# 13_Others.net
KiCad netlist of a schematic drawn in Altium Designer
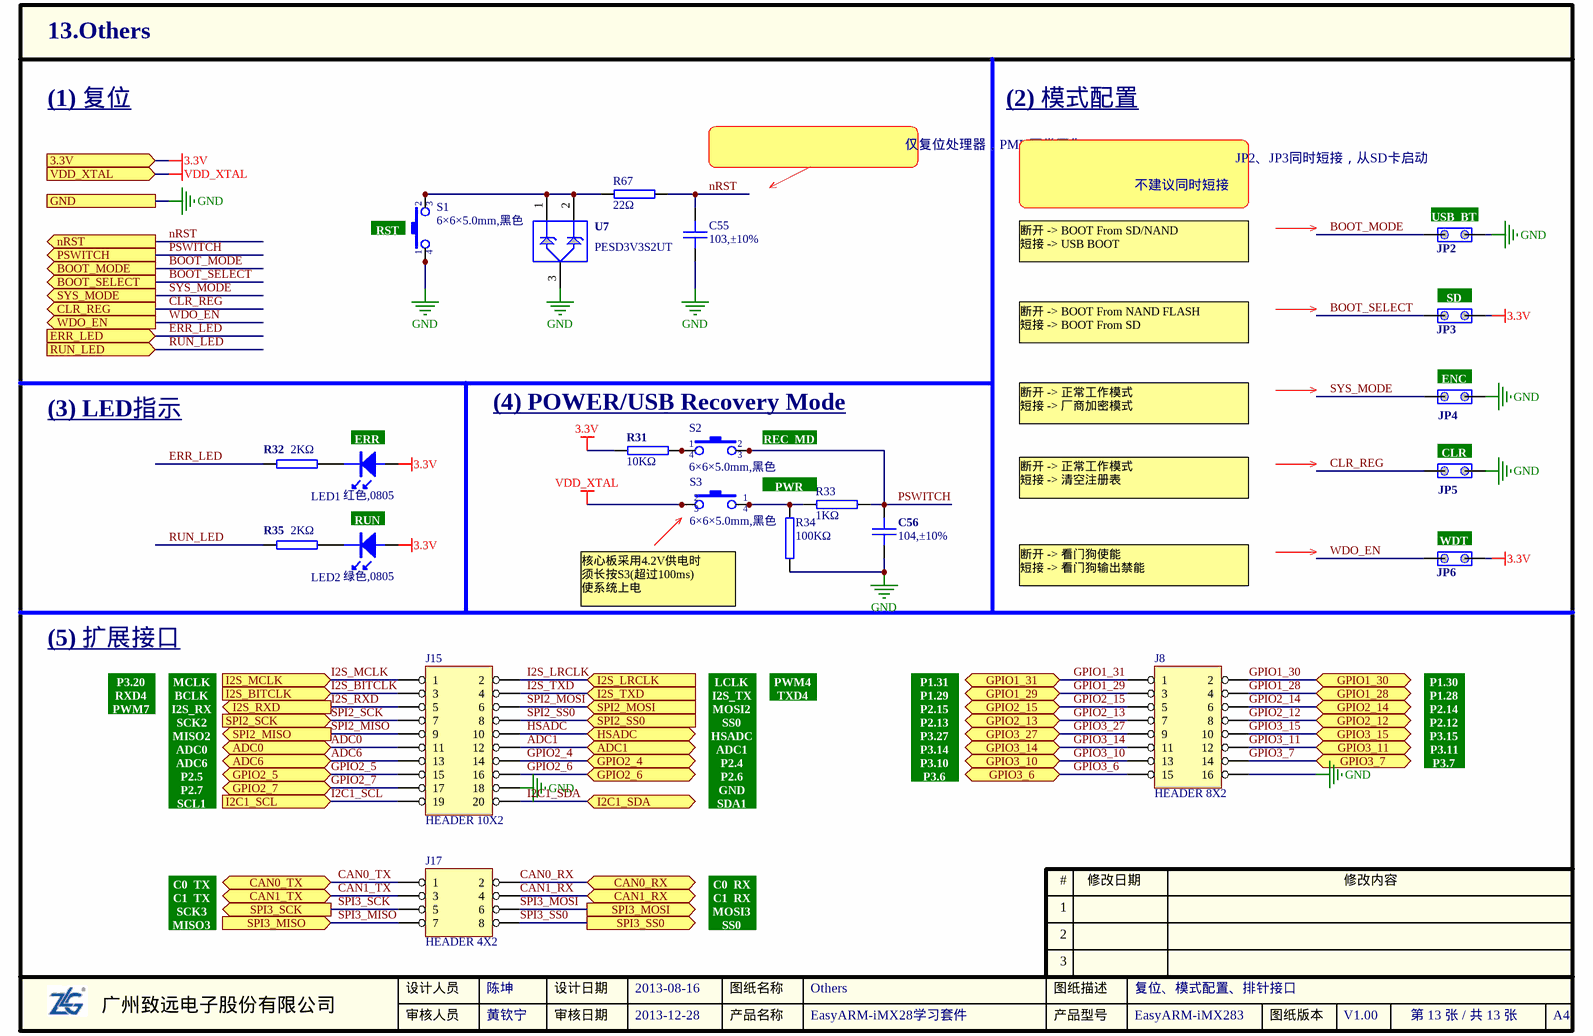
[diagram p0: 13. Others.SchDoc]

(export (version "E")
  (design (tool "Eeschema 10.0.6"))
  (components
    (comp (ref "C55")
      (value "103,±10%")
      (footprint "0603C")
      (description "103,±10%,50V,X7R,0603,*,RoHS")
      (libsource (lib "ErpMaterialData") (part "CAP1"))
    )
    (comp (ref "C56")
      (value "104,±10%")
      (footprint "0603C")
      (description "104,±10%,50V,X7R,0603,*,RoHS")
      (libsource (lib "ErpMaterialData") (part "CAP1"))
    )
    (comp (ref "J8")
      (value "HEADER 8X2")
      (footprint "IDC-16")
      (libsource (lib "无需物料号元件") (part "HEADER 8X2"))
    )
    (comp (ref "J15")
      (value "HEADER 10X2")
      (footprint "IDC-20")
      (libsource (lib "无需物料号元件") (part "HEADER 10X2"))
    )
    (comp (ref "J17")
      (value "HEADER 4X2")
      (footprint "IDC-8")
      (libsource (lib "无需物料号元件") (part "HEADER 4X2"))
    )
    (comp (ref "JP2") (value "120Ω_EN") (footprint "SIP-2") (libsource (lib "无需物料号元件") (part "JMP2")))
    (comp (ref "JP3") (value "120Ω_EN") (footprint "SIP-2") (libsource (lib "无需物料号元件") (part "JMP2")))
    (comp (ref "JP4") (value "120Ω_EN") (footprint "SIP-2") (libsource (lib "无需物料号元件") (part "JMP2")))
    (comp (ref "JP5") (value "120Ω_EN") (footprint "SIP-2") (libsource (lib "无需物料号元件") (part "JMP2")))
    (comp (ref "JP6") (value "120Ω_EN") (footprint "SIP-2") (libsource (lib "无需物料号元件") (part "JMP2")))
    (comp (ref "LED1")
      (value "红色,0805")
      (footprint "LED-0805")
      (description "红色,0805,0805,RoHS")
      (fields (field (name "Comment") "LED1"))
      (libsource (lib "ErpMaterialData") (part "LED1"))
    )
    (comp (ref "LED2")
      (value "绿色,0805")
      (footprint "LED-0805")
      (description "绿色,0805,0805,RoHS")
      (fields (field (name "Comment") "LED1"))
      (libsource (lib "ErpMaterialData") (part "LED1"))
    )
    (comp (ref "R31")
      (value "10KΩ")
      (footprint "0603R")
      (description "10KΩ,0603,*,RoHS")
      (libsource (lib "ErpMaterialData") (part "RES2"))
    )
    (comp (ref "R32")
      (value "2KΩ")
      (footprint "0603R")
      (description "2KΩ,0603,*,RoHS")
      (libsource (lib "ErpMaterialData") (part "RES2"))
    )
    (comp (ref "R33")
      (value "1KΩ")
      (footprint "0603R")
      (description "1KΩ,0603,*,RoHS")
      (libsource (lib "ErpMaterialData") (part "RES2"))
    )
    (comp (ref "R34")
      (value "100KΩ")
      (footprint "0603R")
      (description "100KΩ,0603,*,RoHS")
      (libsource (lib "ErpMaterialData") (part "RES2"))
    )
    (comp (ref "R35")
      (value "2KΩ")
      (footprint "0603R")
      (description "2KΩ,0603,*,RoHS")
      (libsource (lib "ErpMaterialData") (part "RES2"))
    )
    (comp (ref "R67") (value "22Ω") (footprint "0603R") (libsource (lib "ErpMaterialData") (part "RES2")))
    (comp (ref "S1")
      (value "6×6×5.0mm,黑色")
      (footprint "KEY-6S")
      (description "6×6×5.0mm,黑色,SMD,,*")
      (fields (field (name "Comment") "SW-PB4P"))
      (libsource (lib "ErpMaterialData") (part "SW-PB4P"))
    )
    (comp (ref "S2")
      (value "6×6×5.0mm,黑色")
      (footprint "KEY-6S")
      (description "6×6×5.0mm,黑色,SMD,,*")
      (fields (field (name "Comment") "SW-PB4P"))
      (libsource (lib "ErpMaterialData") (part "SW-PB4P"))
    )
    (comp (ref "S3")
      (value "6×6×5.0mm,黑色")
      (footprint "KEY-6S")
      (description "6×6×5.0mm,黑色,SMD,,*")
      (fields (field (name "Comment") "SW-PB4P"))
      (libsource (lib "ErpMaterialData") (part "SW-PB4P"))
    )
    (comp (ref "U7")
      (value "PESD3V3S2UT")
      (footprint "SOT-23")
      (description "ESD单向")
      (fields (field (name "Comment") "ESD-3"))
      (libsource (lib "ErpMaterialData") (part "ESD-3"))
    )
  )
  (nets
    (net (code "1") (name "/ADC0") (class "Default")
      (node (ref "J15") (pin "11") (pinfunction "11_11") (pintype "passive"))
    )
    (net (code "2") (name "/ADC1") (class "Default")
      (node (ref "J15") (pin "12") (pinfunction "12_12") (pintype "passive"))
    )
    (net (code "3") (name "/ADC6") (class "Default")
      (node (ref "J15") (pin "13") (pinfunction "13_13") (pintype "passive"))
    )
    (net (code "4") (name "/BOOT_MODE") (class "Default")
      (node (ref "JP2") (pin "1") (pinfunction "1_1") (pintype "passive"))
    )
    (net (code "5") (name "/BOOT_SELECT") (class "Default")
      (node (ref "JP3") (pin "1") (pinfunction "1_1") (pintype "passive"))
    )
    (net (code "6") (name "/CAN0_RX") (class "Default")
      (node (ref "J17") (pin "2") (pinfunction "2_2") (pintype "passive"))
    )
    (net (code "7") (name "/CAN0_TX") (class "Default")
      (node (ref "J17") (pin "1") (pinfunction "1_1") (pintype "passive"))
    )
    (net (code "8") (name "/CAN1_RX") (class "Default")
      (node (ref "J17") (pin "4") (pinfunction "4_4") (pintype "passive"))
    )
    (net (code "9") (name "/CAN1_TX") (class "Default")
      (node (ref "J17") (pin "3") (pinfunction "3_3") (pintype "passive"))
    )
    (net (code "10") (name "/CLR_REG") (class "Default")
      (node (ref "JP5") (pin "1") (pinfunction "1_1") (pintype "passive"))
    )
    (net (code "11") (name "/ERR_LED") (class "Default")
      (node (ref "R32") (pin "1") (pinfunction "1_1") (pintype "passive"))
    )
    (net (code "12") (name "/GPIO1_28") (class "Default")
      (node (ref "J8") (pin "4") (pinfunction "4_4") (pintype "passive"))
    )
    (net (code "13") (name "/GPIO1_29") (class "Default")
      (node (ref "J8") (pin "3") (pinfunction "3_3") (pintype "passive"))
    )
    (net (code "14") (name "/GPIO1_30") (class "Default")
      (node (ref "J8") (pin "2") (pinfunction "2_2") (pintype "passive"))
    )
    (net (code "15") (name "/GPIO1_31") (class "Default")
      (node (ref "J8") (pin "1") (pinfunction "1_1") (pintype "passive"))
    )
    (net (code "16") (name "/GPIO2_4") (class "Default")
      (node (ref "J15") (pin "14") (pinfunction "14_14") (pintype "passive"))
    )
    (net (code "17") (name "/GPIO2_5") (class "Default")
      (node (ref "J15") (pin "15") (pinfunction "15_15") (pintype "passive"))
    )
    (net (code "18") (name "/GPIO2_6") (class "Default")
      (node (ref "J15") (pin "16") (pinfunction "16_16") (pintype "passive"))
    )
    (net (code "19") (name "/GPIO2_7") (class "Default")
      (node (ref "J15") (pin "17") (pinfunction "17_17") (pintype "passive"))
    )
    (net (code "20") (name "/GPIO2_12") (class "Default")
      (node (ref "J8") (pin "8") (pinfunction "8_8") (pintype "passive"))
    )
    (net (code "21") (name "/GPIO2_13") (class "Default")
      (node (ref "J8") (pin "7") (pinfunction "7_7") (pintype "passive"))
    )
    (net (code "22") (name "/GPIO2_14") (class "Default")
      (node (ref "J8") (pin "6") (pinfunction "6_6") (pintype "passive"))
    )
    (net (code "23") (name "/GPIO2_15") (class "Default")
      (node (ref "J8") (pin "5") (pinfunction "5_5") (pintype "passive"))
    )
    (net (code "24") (name "/GPIO3_6") (class "Default")
      (node (ref "J8") (pin "15") (pinfunction "15_15") (pintype "passive"))
    )
    (net (code "25") (name "/GPIO3_7") (class "Default")
      (node (ref "J8") (pin "14") (pinfunction "14_14") (pintype "passive"))
    )
    (net (code "26") (name "/GPIO3_10") (class "Default")
      (node (ref "J8") (pin "13") (pinfunction "13_13") (pintype "passive"))
    )
    (net (code "27") (name "/GPIO3_11") (class "Default")
      (node (ref "J8") (pin "12") (pinfunction "12_12") (pintype "passive"))
    )
    (net (code "28") (name "/GPIO3_14") (class "Default")
      (node (ref "J8") (pin "11") (pinfunction "11_11") (pintype "passive"))
    )
    (net (code "29") (name "/GPIO3_15") (class "Default")
      (node (ref "J8") (pin "10") (pinfunction "10_10") (pintype "passive"))
    )
    (net (code "30") (name "/GPIO3_27") (class "Default")
      (node (ref "J8") (pin "9") (pinfunction "9_9") (pintype "passive"))
    )
    (net (code "31") (name "/HSADC") (class "Default")
      (node (ref "J15") (pin "10") (pinfunction "10_10") (pintype "passive"))
    )
    (net (code "32") (name "/I2C1_SCL") (class "Default")
      (node (ref "J15") (pin "19") (pinfunction "19_19") (pintype "passive"))
    )
    (net (code "33") (name "/I2C1_SDA") (class "Default")
      (node (ref "J15") (pin "20") (pinfunction "20_20") (pintype "passive"))
    )
    (net (code "34") (name "/I2S_BITCLK") (class "Default")
      (node (ref "J15") (pin "3") (pinfunction "3_3") (pintype "passive"))
    )
    (net (code "35") (name "/I2S_LRCLK") (class "Default")
      (node (ref "J15") (pin "2") (pinfunction "2_2") (pintype "passive"))
    )
    (net (code "36") (name "/I2S_MCLK") (class "Default")
      (node (ref "J15") (pin "1") (pinfunction "1_1") (pintype "passive"))
    )
    (net (code "37") (name "/I2S_RXD") (class "Default")
      (node (ref "J15") (pin "5") (pinfunction "5_5") (pintype "passive"))
    )
    (net (code "38") (name "/I2S_TXD") (class "Default")
      (node (ref "J15") (pin "4") (pinfunction "4_4") (pintype "passive"))
    )
    (net (code "39") (name "/PSWITCH") (class "Default")
      (node (ref "C56") (pin "2") (pinfunction "2_2") (pintype "passive"))
      (node (ref "R33") (pin "2") (pinfunction "2_2") (pintype "passive"))
      (node (ref "S2") (pin "2") (pinfunction "2_2") (pintype "passive"))
      (node (ref "S2") (pin "3") (pinfunction "3_3") (pintype "passive"))
    )
    (net (code "40") (name "/RUN_LED") (class "Default")
      (node (ref "R35") (pin "1") (pinfunction "1_1") (pintype "passive"))
    )
    (net (code "41") (name "/SPI2_MISO") (class "Default")
      (node (ref "J15") (pin "9") (pinfunction "9_9") (pintype "passive"))
    )
    (net (code "42") (name "/SPI2_MOSI") (class "Default")
      (node (ref "J15") (pin "6") (pinfunction "6_6") (pintype "passive"))
    )
    (net (code "43") (name "/SPI2_SCK") (class "Default")
      (node (ref "J15") (pin "7") (pinfunction "7_7") (pintype "passive"))
    )
    (net (code "44") (name "/SPI2_SS0") (class "Default")
      (node (ref "J15") (pin "8") (pinfunction "8_8") (pintype "passive"))
    )
    (net (code "45") (name "/SPI3_MISO") (class "Default")
      (node (ref "J17") (pin "7") (pinfunction "7_7") (pintype "passive"))
    )
    (net (code "46") (name "/SPI3_MOSI") (class "Default")
      (node (ref "J17") (pin "6") (pinfunction "6_6") (pintype "passive"))
    )
    (net (code "47") (name "/SPI3_SCK") (class "Default")
      (node (ref "J17") (pin "5") (pinfunction "5_5") (pintype "passive"))
    )
    (net (code "48") (name "/SPI3_SS0") (class "Default")
      (node (ref "J17") (pin "8") (pinfunction "8_8") (pintype "passive"))
    )
    (net (code "49") (name "/SYS_MODE") (class "Default")
      (node (ref "JP4") (pin "1") (pinfunction "1_1") (pintype "passive"))
    )
    (net (code "50") (name "/WDO_EN") (class "Default")
      (node (ref "JP6") (pin "1") (pinfunction "1_1") (pintype "passive"))
    )
    (net (code "51") (name "/nRST") (class "Default")
      (node (ref "C55") (pin "1") (pinfunction "1_1") (pintype "passive"))
      (node (ref "R67") (pin "1") (pinfunction "1_1") (pintype "passive"))
    )
    (net (code "52") (name "3.3V") (class "Default")
      (node (ref "JP3") (pin "2") (pinfunction "2_2") (pintype "passive"))
      (node (ref "JP6") (pin "2") (pinfunction "2_2") (pintype "passive"))
      (node (ref "LED1") (pin "1") (pinfunction "1_1") (pintype "passive"))
      (node (ref "LED2") (pin "1") (pinfunction "1_1") (pintype "passive"))
      (node (ref "R31") (pin "1") (pinfunction "1_1") (pintype "passive"))
    )
    (net (code "53") (name "GND") (class "Default")
      (node (ref "C55") (pin "2") (pinfunction "2_2") (pintype "passive"))
      (node (ref "C56") (pin "1") (pinfunction "1_1") (pintype "passive"))
      (node (ref "J15") (pin "18") (pinfunction "18_18") (pintype "passive"))
      (node (ref "J8") (pin "16") (pinfunction "16_16") (pintype "passive"))
      (node (ref "JP2") (pin "2") (pinfunction "2_2") (pintype "passive"))
      (node (ref "JP4") (pin "2") (pinfunction "2_2") (pintype "passive"))
      (node (ref "JP5") (pin "2") (pinfunction "2_2") (pintype "passive"))
      (node (ref "R34") (pin "2") (pinfunction "2_2") (pintype "passive"))
      (node (ref "S1") (pin "1") (pinfunction "1_1") (pintype "passive"))
      (node (ref "S1") (pin "4") (pinfunction "4_4") (pintype "passive"))
      (node (ref "U7") (pin "3") (pinfunction "3_3") (pintype "passive"))
    )
    (net (code "54") (name "Net-(LED1-Pad2)") (class "Default")
      (node (ref "LED1") (pin "2") (pinfunction "2_2") (pintype "passive"))
      (node (ref "R32") (pin "2") (pinfunction "2_2") (pintype "passive"))
    )
    (net (code "55") (name "Net-(LED2-Pad2)") (class "Default")
      (node (ref "LED2") (pin "2") (pinfunction "2_2") (pintype "passive"))
      (node (ref "R35") (pin "2") (pinfunction "2_2") (pintype "passive"))
    )
    (net (code "56") (name "Net-(R31-Pad2)") (class "Default")
      (node (ref "R31") (pin "2") (pinfunction "2_2") (pintype "passive"))
      (node (ref "S2") (pin "1") (pinfunction "1_1") (pintype "passive"))
      (node (ref "S2") (pin "4") (pinfunction "4_4") (pintype "passive"))
    )
    (net (code "57") (name "Net-(R33-Pad1)") (class "Default")
      (node (ref "R33") (pin "1") (pinfunction "1_1") (pintype "passive"))
      (node (ref "R34") (pin "1") (pinfunction "1_1") (pintype "passive"))
      (node (ref "S3") (pin "1") (pinfunction "1_1") (pintype "passive"))
      (node (ref "S3") (pin "4") (pinfunction "4_4") (pintype "passive"))
    )
    (net (code "58") (name "Net-(R67-Pad2)") (class "Default")
      (node (ref "R67") (pin "2") (pinfunction "2_2") (pintype "passive"))
      (node (ref "S1") (pin "2") (pinfunction "2_2") (pintype "passive"))
      (node (ref "S1") (pin "3") (pinfunction "3_3") (pintype "passive"))
      (node (ref "U7") (pin "1") (pinfunction "1_1") (pintype "passive"))
      (node (ref "U7") (pin "2") (pinfunction "2_2") (pintype "passive"))
    )
    (net (code "59") (name "VDD_XTAL") (class "Default")
      (node (ref "S3") (pin "2") (pinfunction "2_2") (pintype "passive"))
      (node (ref "S3") (pin "3") (pinfunction "3_3") (pintype "passive"))
    )
  )
)
